# pca64110.net
KiCad netlist of a schematic drawn in Altium Designer
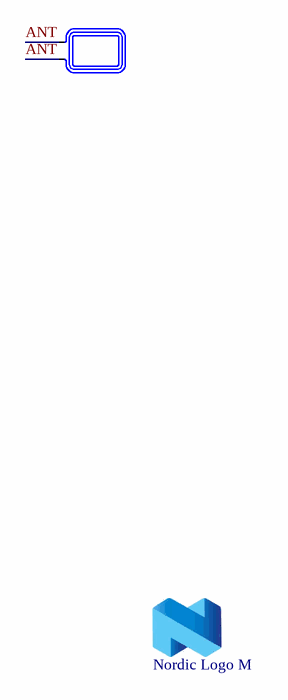
[diagram p0: pca64110.SchDoc]

(export (version "E")
  (design (tool "Eeschema 10.0.6"))
  (components
    (comp (ref "A1")
      (value "NFC_ANT_Listener-6")
      (footprint "NFC_ANT_Listener-6")
      (description "NFC Antenna Listener-6")
      (fields (field (name "PUBLISHER") "Nordic Semiconductor"))
      (libsource (lib "Nordic Passive DB") (part "NFC_Antenna"))
    )
    (comp (ref "LOGO1")
      (value "Nordic Logo M")
      (footprint "NORDIC_LOGO_M")
      (description "Nordic Logo, medium size")
      (fields (field (name "PUBLISHER") "Nordic Semiconductor"))
      (libsource (lib "Nordic Passive DB") (part "Nordic Logo"))
    )
  )
  (nets
    (net (code "1") (name "/ANT") (class "Default")
      (node (ref "A1") (pin "1") (pinfunction "1_1") (pintype "passive"))
      (node (ref "A1") (pin "2") (pinfunction "2_2") (pintype "passive"))
    )
  )
)
